# Power_Distribution.net
KiCad netlist of a schematic drawn in Altium Designer
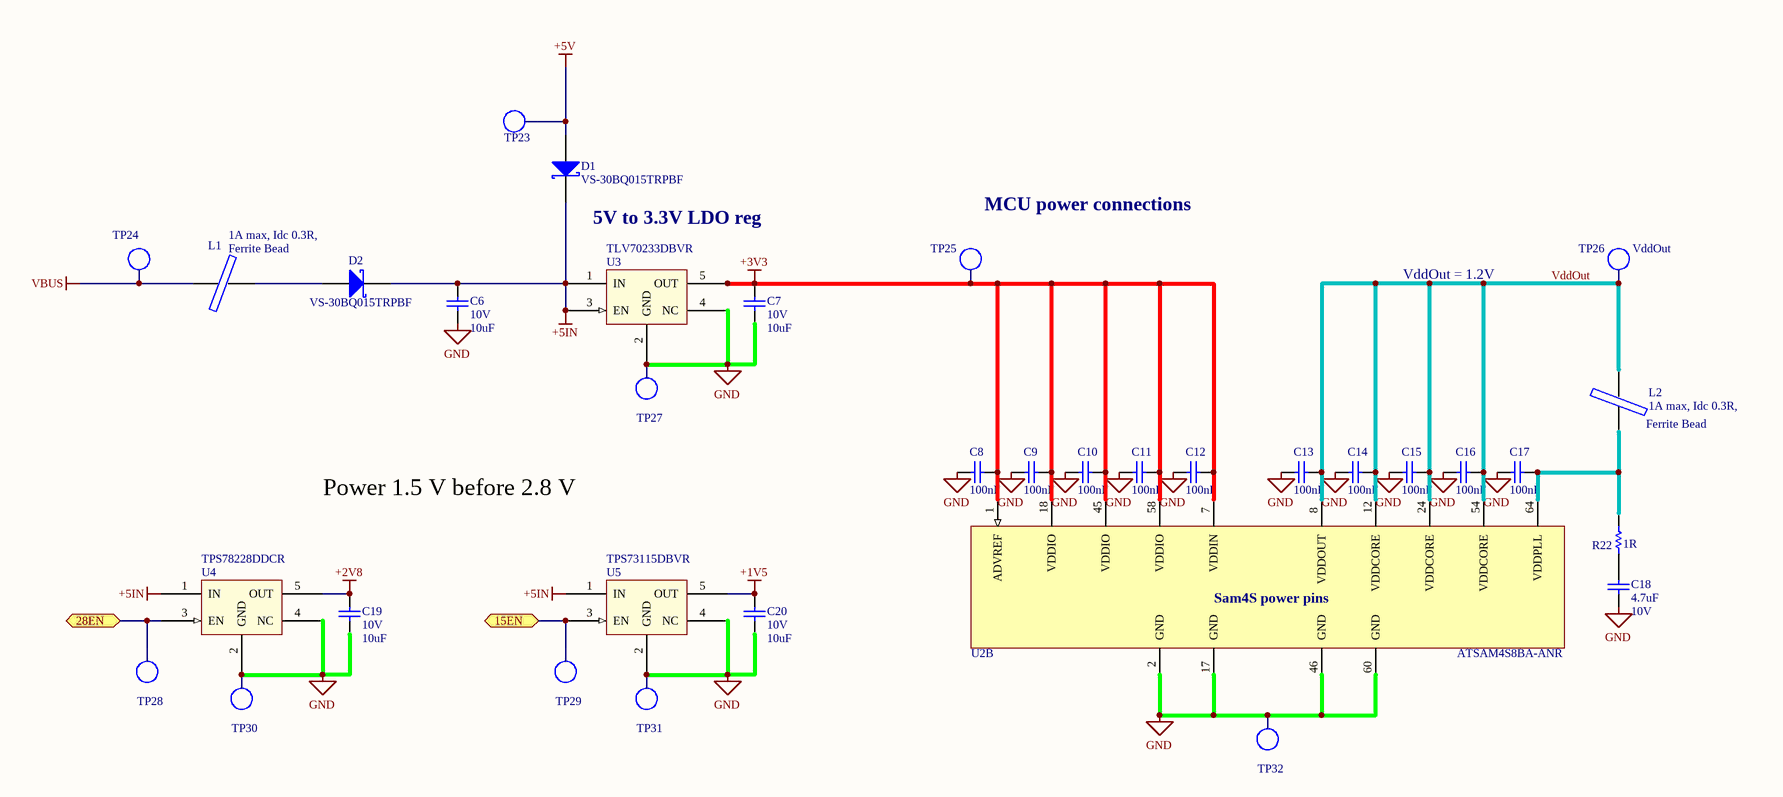
[diagram p0: Power_Distribution.SchDoc]

(export (version "E")
  (design (tool "Eeschema 10.0.6"))
  (components
    (comp (ref "C6")
      (value "10uF")
      (footprint "ECE Components_16_2:CAPC1608L")
      (description "CAP CER 10UF X5R +-20% 10V 0603")
      (fields (field (name "VOLTAGE - RATED") "10V"))
      (libsource (lib "ECE Components_15_7") (part "CC_10uF_0603"))
    )
    (comp (ref "C7")
      (value "10uF")
      (footprint "ECE Components_16_2:CAPC1608L")
      (description "CAP CER 10UF X5R +-20% 10V 0603")
      (fields (field (name "VOLTAGE - RATED") "10V"))
      (libsource (lib "ECE Components_15_7") (part "CC_10uF_0603"))
    )
    (comp (ref "C8")
      (value "100nF")
      (footprint "ECE Components_16_2:CAPC1608L")
      (description "CAP CER 100nF X7R +-10% 50V 0603")
      (libsource (lib "ECE Components_15_7") (part "CC_100nF_0603"))
    )
    (comp (ref "C9")
      (value "100nF")
      (footprint "ECE Components_16_2:CAPC1608L")
      (description "CAP CER 100nF X7R +-10% 50V 0603")
      (libsource (lib "ECE Components_15_7") (part "CC_100nF_0603"))
    )
    (comp (ref "C10")
      (value "100nF")
      (footprint "ECE Components_16_2:CAPC1608L")
      (description "CAP CER 100nF X7R +-10% 50V 0603")
      (libsource (lib "ECE Components_15_7") (part "CC_100nF_0603"))
    )
    (comp (ref "C11")
      (value "100nF")
      (footprint "ECE Components_16_2:CAPC1608L")
      (description "CAP CER 100nF X7R +-10% 50V 0603")
      (libsource (lib "ECE Components_15_7") (part "CC_100nF_0603"))
    )
    (comp (ref "C12")
      (value "100nF")
      (footprint "ECE Components_16_2:CAPC1608L")
      (description "CAP CER 100nF X7R +-10% 50V 0603")
      (libsource (lib "ECE Components_15_7") (part "CC_100nF_0603"))
    )
    (comp (ref "C13")
      (value "100nF")
      (footprint "ECE Components_16_2:CAPC1608L")
      (description "CAP CER 100nF X7R +-10% 50V 0603")
      (libsource (lib "ECE Components_15_7") (part "CC_100nF_0603"))
    )
    (comp (ref "C14")
      (value "100nF")
      (footprint "ECE Components_16_2:CAPC1608L")
      (description "CAP CER 100nF X7R +-10% 50V 0603")
      (libsource (lib "ECE Components_15_7") (part "CC_100nF_0603"))
    )
    (comp (ref "C15")
      (value "100nF")
      (footprint "ECE Components_16_2:CAPC1608L")
      (description "CAP CER 100nF X7R +-10% 50V 0603")
      (libsource (lib "ECE Components_15_7") (part "CC_100nF_0603"))
    )
    (comp (ref "C16")
      (value "100nF")
      (footprint "ECE Components_16_2:CAPC1608L")
      (description "CAP CER 100nF X7R +-10% 50V 0603")
      (libsource (lib "ECE Components_15_7") (part "CC_100nF_0603"))
    )
    (comp (ref "C17")
      (value "100nF")
      (footprint "ECE Components_16_2:CAPC1608L")
      (description "CAP CER 100nF X7R +-10% 50V 0603")
      (libsource (lib "ECE Components_15_7") (part "CC_100nF_0603"))
    )
    (comp (ref "C18")
      (value "4.7uF")
      (footprint "ECE Components_16_2:CAPC1608N")
      (description "CAP CER 4.7uF X5R +-20%  10V 0603")
      (fields (field (name "MAX VOLTAGE") "10V"))
      (libsource (lib "ECE Components_15_7") (part "CC_4.7uF_0603"))
    )
    (comp (ref "C19")
      (value "10uF")
      (footprint "ECE Components_16_2:CAPC1608L")
      (description "CAP CER 10UF X5R +-20% 10V 0603")
      (fields (field (name "VOLTAGE - RATED") "10V"))
      (libsource (lib "ECE Components_15_7") (part "CC_10uF_0603"))
    )
    (comp (ref "C20")
      (value "10uF")
      (footprint "ECE Components_16_2:CAPC1608L")
      (description "CAP CER 10UF X5R +-20% 10V 0603")
      (fields (field (name "VOLTAGE - RATED") "10V"))
      (libsource (lib "ECE Components_15_7") (part "CC_10uF_0603"))
    )
    (comp (ref "D1")
      (value "VS-30BQ015TRPBF")
      (footprint "SMC")
      (description "DIODE SCHOTTKY 15V 3A SMC")
      (fields
        (field (name "MANUFACTURER") "Vishay Semiconductor Diodes Division")
        (field (name "MANUFACTURER PART NUMBER") "VS-30BQ015TRPBF")
      )
      (libsource (lib "ECE Components_16_2") (part "DS_VS-30BQD015TRPBF"))
    )
    (comp (ref "D2")
      (value "VS-30BQ015TRPBF")
      (footprint "SMC")
      (description "DIODE SCHOTTKY 15V 3A SMC")
      (fields
        (field (name "MANUFACTURER") "Vishay Semiconductor Diodes Division")
        (field (name "MANUFACTURER PART NUMBER") "VS-30BQ015TRPBF")
      )
      (libsource (lib "ECE Components_16_2") (part "DS_VS-30BQD015TRPBF"))
    )
    (comp (ref "L1")
      (value "Ferrite Bead")
      (footprint "ECE Components_16_2:INDC3216L")
      (description "Ferrite Bead, Rdc 0.3R, Z100MHZ 600R, Imax 1A, SMD 1206")
      (fields
        (field (name "MANUFACTURER") "FAIR-RITE")
        (field (name "MANUFACTURER PART NUMBER") "2512066017Y1")
        (field (name "ALTIUM_VALUE") "1A max, Idc 0.3R,")
      )
      (libsource (lib "ECE Components_15_7") (part "IN_Ferrite-Bead"))
    )
    (comp (ref "L2")
      (value "Ferrite Bead")
      (footprint "ECE Components_16_2:INDC3216L")
      (description "Ferrite Bead, Rdc 0.3R, Z100MHZ 600R, Imax 1A, SMD 1206")
      (fields
        (field (name "MANUFACTURER") "FAIR-RITE")
        (field (name "MANUFACTURER PART NUMBER") "2512066017Y1")
        (field (name "ALTIUM_VALUE") "1A max, Idc 0.3R,")
      )
      (libsource (lib "ECE Components_15_7") (part "IN_Ferrite-Bead"))
    )
    (comp (ref "R22")
      (value "1R")
      (footprint "ECE Components_16_2:RESC3216L")
      (description "RES 1R OHM 1/4W 5% 1206 SMD")
      (libsource (lib "ECE Components_15_7") (part "RT_1R"))
    )
    (comp (ref "TP23")
      (value "V_Bus")
      (footprint "ECE Components_16_2:TP_0805")
      (description "Test Point 2.0X0.9X1.2mm SMD")
      (fields
        (field (name "MANUFACTURER") "TE Connectivity AMP Connectors")
        (field (name "MANUFACTURER PART NUMBER") "1625854-2")
      )
      (libsource (lib "ECE Components_15_7") (part "TP_0805"))
    )
    (comp (ref "TP24")
      (value "V_Bus")
      (footprint "ECE Components_16_2:TP_0805")
      (description "Test Point 2.0X0.9X1.2mm SMD")
      (fields
        (field (name "MANUFACTURER") "TE Connectivity AMP Connectors")
        (field (name "MANUFACTURER PART NUMBER") "1625854-2")
      )
      (libsource (lib "ECE Components_15_7") (part "TP_0805"))
    )
    (comp (ref "TP25")
      (value "3V3")
      (footprint "ECE Components_16_2:TP_0805")
      (description "Test Point 2.0X0.9X1.2mm SMD")
      (fields
        (field (name "MANUFACTURER") "TE Connectivity AMP Connectors")
        (field (name "MANUFACTURER PART NUMBER") "1625854-2")
      )
      (libsource (lib "ECE Components_15_7") (part "TP_0805"))
    )
    (comp (ref "TP26")
      (value "VddOut")
      (footprint "ECE Components_16_2:TP_0805")
      (description "Test Point 2.0X0.9X1.2mm SMD")
      (fields
        (field (name "MANUFACTURER") "TE Connectivity AMP Connectors")
        (field (name "MANUFACTURER PART NUMBER") "1625854-2")
      )
      (libsource (lib "ECE Components_15_7") (part "TP_0805"))
    )
    (comp (ref "TP27")
      (value "Gnd")
      (footprint "ECE Components_16_2:TP_0805")
      (description "Test Point 2.0X0.9X1.2mm SMD")
      (fields
        (field (name "MANUFACTURER") "TE Connectivity AMP Connectors")
        (field (name "MANUFACTURER PART NUMBER") "1625854-2")
      )
      (libsource (lib "ECE Components_15_7") (part "TP_0805"))
    )
    (comp (ref "TP28")
      (value "Gnd")
      (footprint "ECE Components_16_2:TP_0805")
      (description "Test Point 2.0X0.9X1.2mm SMD")
      (fields
        (field (name "MANUFACTURER") "TE Connectivity AMP Connectors")
        (field (name "MANUFACTURER PART NUMBER") "1625854-2")
      )
      (libsource (lib "ECE Components_15_7") (part "TP_0805"))
    )
    (comp (ref "TP29")
      (value "Gnd")
      (footprint "ECE Components_16_2:TP_0805")
      (description "Test Point 2.0X0.9X1.2mm SMD")
      (fields
        (field (name "MANUFACTURER") "TE Connectivity AMP Connectors")
        (field (name "MANUFACTURER PART NUMBER") "1625854-2")
      )
      (libsource (lib "ECE Components_15_7") (part "TP_0805"))
    )
    (comp (ref "TP30")
      (value "Gnd")
      (footprint "ECE Components_16_2:TP_0805")
      (description "Test Point 2.0X0.9X1.2mm SMD")
      (fields
        (field (name "MANUFACTURER") "TE Connectivity AMP Connectors")
        (field (name "MANUFACTURER PART NUMBER") "1625854-2")
      )
      (libsource (lib "ECE Components_15_7") (part "TP_0805"))
    )
    (comp (ref "TP31")
      (value "Gnd")
      (footprint "ECE Components_16_2:TP_0805")
      (description "Test Point 2.0X0.9X1.2mm SMD")
      (fields
        (field (name "MANUFACTURER") "TE Connectivity AMP Connectors")
        (field (name "MANUFACTURER PART NUMBER") "1625854-2")
      )
      (libsource (lib "ECE Components_15_7") (part "TP_0805"))
    )
    (comp (ref "TP32")
      (value "Gnd")
      (footprint "ECE Components_16_2:TP_0805")
      (description "Test Point 2.0X0.9X1.2mm SMD")
      (fields
        (field (name "MANUFACTURER") "TE Connectivity AMP Connectors")
        (field (name "MANUFACTURER PART NUMBER") "1625854-2")
      )
      (libsource (lib "ECE Components_15_7") (part "TP_0805"))
    )
    (comp (ref "U2")
      (value "ATSAM4S8BA-ANR")
      (footprint "ECE Components_16_2:LQFP64_L")
      (description "IC MCU 32BIT 512KB FLASH 64LQFP")
      (fields (field (name "MANUFACTURER") "Atmel"))
      (libsource (lib "ECE Components_15_7") (part "SE_ATSAM4S16BA-MU"))
    )
    (comp (ref "U3")
      (value "TLV70233DBVR")
      (footprint "ECE Components_16_2:SOT95P280X145-5N")
      (description "IC REG LDO 3.3V 0.3A SOT23-5")
      (fields
        (field (name "MANUFACTURER") "Texas Instruments")
        (field (name "MANUFACTURER PART NUMBER") "TLV70233DBVR")
      )
      (libsource (lib "ECE Components_15_7") (part "SV_TLV70233DBVR"))
    )
    (comp (ref "U4")
      (value "TPS78228DDCR")
      (footprint "ECE Components_16_2:SOT95P280X145-5N")
      (description "IC REG LDO 2.8V 0.3A SOT23-5")
      (fields
        (field (name "MANUFACTURER") "Texas Instruments")
        (field (name "MANUFACTURER PART NUMBER") "TPS78228DDCR")
      )
      (libsource (lib "ECE Components_15_7") (part "SV_TLV70233DBVR"))
    )
    (comp (ref "U5")
      (value "TPS73115DBVR")
      (footprint "ECE Components_16_2:SOT95P280X145-5N")
      (description "IC REG LDO 1.5V 0.3A SOT23-5")
      (fields
        (field (name "MANUFACTURER") "Texas Instruments")
        (field (name "MANUFACTURER PART NUMBER") "TPS73115DBVR")
      )
      (libsource (lib "ECE Components_15_7") (part "SV_TLV70233DBVR"))
    )
  )
  (nets
    (net (code "1") (name "+1V5") (class "Default")
      (node (ref "C20") (pin "1") (pinfunction "1_1") (pintype "passive"))
      (node (ref "U5") (pin "5") (pinfunction "OUT_5") (pintype "power_in"))
    )
    (net (code "2") (name "+2V8") (class "Default")
      (node (ref "C19") (pin "1") (pinfunction "1_1") (pintype "passive"))
      (node (ref "U4") (pin "5") (pinfunction "OUT_5") (pintype "power_in"))
    )
    (net (code "3") (name "+3V3") (class "Default")
      (node (ref "C10") (pin "2") (pinfunction "2_2") (pintype "passive"))
      (node (ref "C11") (pin "2") (pinfunction "2_2") (pintype "passive"))
      (node (ref "C12") (pin "2") (pinfunction "2_2") (pintype "passive"))
      (node (ref "C7") (pin "1") (pinfunction "1_1") (pintype "passive"))
      (node (ref "C8") (pin "2") (pinfunction "2_2") (pintype "passive"))
      (node (ref "C9") (pin "2") (pinfunction "2_2") (pintype "passive"))
      (node (ref "TP25") (pin "1") (pinfunction "TP_1") (pintype "passive"))
      (node (ref "U2") (pin "1") (pinfunction "ADVREF_1") (pintype "input"))
      (node (ref "U2") (pin "18") (pinfunction "VDDIO_18") (pintype "power_in"))
      (node (ref "U2") (pin "45") (pinfunction "VDDIO_45") (pintype "power_in"))
      (node (ref "U2") (pin "58") (pinfunction "VDDIO_58") (pintype "power_in"))
      (node (ref "U2") (pin "7") (pinfunction "VDDIN_7") (pintype "power_in"))
      (node (ref "U3") (pin "5") (pinfunction "OUT_5") (pintype "power_in"))
    )
    (net (code "4") (name "+5IN") (class "Default")
      (node (ref "C6") (pin "1") (pinfunction "1_1") (pintype "passive"))
      (node (ref "D1") (pin "2") (pinfunction "K_2") (pintype "passive"))
      (node (ref "D2") (pin "2") (pinfunction "K_2") (pintype "passive"))
      (node (ref "U3") (pin "1") (pinfunction "IN_1") (pintype "power_in"))
      (node (ref "U3") (pin "3") (pinfunction "EN_3") (pintype "input"))
      (node (ref "U4") (pin "1") (pinfunction "IN_1") (pintype "power_in"))
      (node (ref "U5") (pin "1") (pinfunction "IN_1") (pintype "power_in"))
    )
    (net (code "5") (name "+5V") (class "Default")
      (node (ref "D1") (pin "1") (pinfunction "A_1") (pintype "passive"))
      (node (ref "TP23") (pin "1") (pinfunction "TP_1") (pintype "passive"))
    )
    (net (code "6") (name "/15EN") (class "Default")
      (node (ref "TP29") (pin "1") (pinfunction "TP_1") (pintype "passive"))
      (node (ref "U5") (pin "3") (pinfunction "EN_3") (pintype "input"))
    )
    (net (code "7") (name "/28EN") (class "Default")
      (node (ref "TP28") (pin "1") (pinfunction "TP_1") (pintype "passive"))
      (node (ref "U4") (pin "3") (pinfunction "EN_3") (pintype "input"))
    )
    (net (code "8") (name "/VddOut") (class "Default")
      (node (ref "C13") (pin "2") (pinfunction "2_2") (pintype "passive"))
      (node (ref "C14") (pin "2") (pinfunction "2_2") (pintype "passive"))
      (node (ref "C15") (pin "2") (pinfunction "2_2") (pintype "passive"))
      (node (ref "C16") (pin "2") (pinfunction "2_2") (pintype "passive"))
      (node (ref "L2") (pin "2") (pinfunction "2_2") (pintype "passive"))
      (node (ref "TP26") (pin "1") (pinfunction "TP_1") (pintype "passive"))
      (node (ref "U2") (pin "12") (pinfunction "VDDCORE_12") (pintype "power_in"))
      (node (ref "U2") (pin "24") (pinfunction "VDDCORE_24") (pintype "power_in"))
      (node (ref "U2") (pin "54") (pinfunction "VDDCORE_54") (pintype "power_in"))
      (node (ref "U2") (pin "8") (pinfunction "VDDOUT_8") (pintype "power_in"))
    )
    (net (code "9") (name "GND") (class "Default")
      (node (ref "C10") (pin "1") (pinfunction "1_1") (pintype "passive"))
      (node (ref "C11") (pin "1") (pinfunction "1_1") (pintype "passive"))
      (node (ref "C12") (pin "1") (pinfunction "1_1") (pintype "passive"))
      (node (ref "C13") (pin "1") (pinfunction "1_1") (pintype "passive"))
      (node (ref "C14") (pin "1") (pinfunction "1_1") (pintype "passive"))
      (node (ref "C15") (pin "1") (pinfunction "1_1") (pintype "passive"))
      (node (ref "C16") (pin "1") (pinfunction "1_1") (pintype "passive"))
      (node (ref "C17") (pin "1") (pinfunction "1_1") (pintype "passive"))
      (node (ref "C18") (pin "1") (pinfunction "1_1") (pintype "passive"))
      (node (ref "C19") (pin "2") (pinfunction "2_2") (pintype "passive"))
      (node (ref "C20") (pin "2") (pinfunction "2_2") (pintype "passive"))
      (node (ref "C6") (pin "2") (pinfunction "2_2") (pintype "passive"))
      (node (ref "C7") (pin "2") (pinfunction "2_2") (pintype "passive"))
      (node (ref "C8") (pin "1") (pinfunction "1_1") (pintype "passive"))
      (node (ref "C9") (pin "1") (pinfunction "1_1") (pintype "passive"))
      (node (ref "TP27") (pin "1") (pinfunction "TP_1") (pintype "passive"))
      (node (ref "TP30") (pin "1") (pinfunction "TP_1") (pintype "passive"))
      (node (ref "TP31") (pin "1") (pinfunction "TP_1") (pintype "passive"))
      (node (ref "TP32") (pin "1") (pinfunction "TP_1") (pintype "passive"))
      (node (ref "U2") (pin "17") (pinfunction "GND_17") (pintype "power_in"))
      (node (ref "U2") (pin "2") (pinfunction "GND_2") (pintype "power_in"))
      (node (ref "U2") (pin "46") (pinfunction "GND_46") (pintype "power_in"))
      (node (ref "U2") (pin "60") (pinfunction "GND_60") (pintype "power_in"))
      (node (ref "U3") (pin "2") (pinfunction "GND_2") (pintype "power_in"))
      (node (ref "U3") (pin "4") (pinfunction "NC_4") (pintype "passive"))
      (node (ref "U4") (pin "2") (pinfunction "GND_2") (pintype "power_in"))
      (node (ref "U4") (pin "4") (pinfunction "NC_4") (pintype "passive"))
      (node (ref "U5") (pin "2") (pinfunction "GND_2") (pintype "power_in"))
      (node (ref "U5") (pin "4") (pinfunction "NC_4") (pintype "passive"))
    )
    (net (code "10") (name "Net-(C18-Pad2)") (class "Default")
      (node (ref "C18") (pin "2") (pinfunction "2_2") (pintype "passive"))
      (node (ref "R22") (pin "1") (pinfunction "1_1") (pintype "passive"))
    )
    (net (code "11") (name "Net-(D2-A)") (class "Default")
      (node (ref "D2") (pin "1") (pinfunction "A_1") (pintype "passive"))
      (node (ref "L1") (pin "2") (pinfunction "2_2") (pintype "passive"))
    )
    (net (code "12") (name "Net-(U2B-VDDPLL)") (class "Default")
      (node (ref "C17") (pin "2") (pinfunction "2_2") (pintype "passive"))
      (node (ref "L2") (pin "1") (pinfunction "1_1") (pintype "passive"))
      (node (ref "R22") (pin "2") (pinfunction "2_2") (pintype "passive"))
      (node (ref "U2") (pin "64") (pinfunction "VDDPLL_64") (pintype "power_in"))
    )
    (net (code "13") (name "VBUS") (class "Default")
      (node (ref "L1") (pin "1") (pinfunction "1_1") (pintype "passive"))
      (node (ref "TP24") (pin "1") (pinfunction "TP_1") (pintype "passive"))
    )
  )
)
